# MatchboxARM.net
KiCad netlist of a schematic drawn in EAGLE
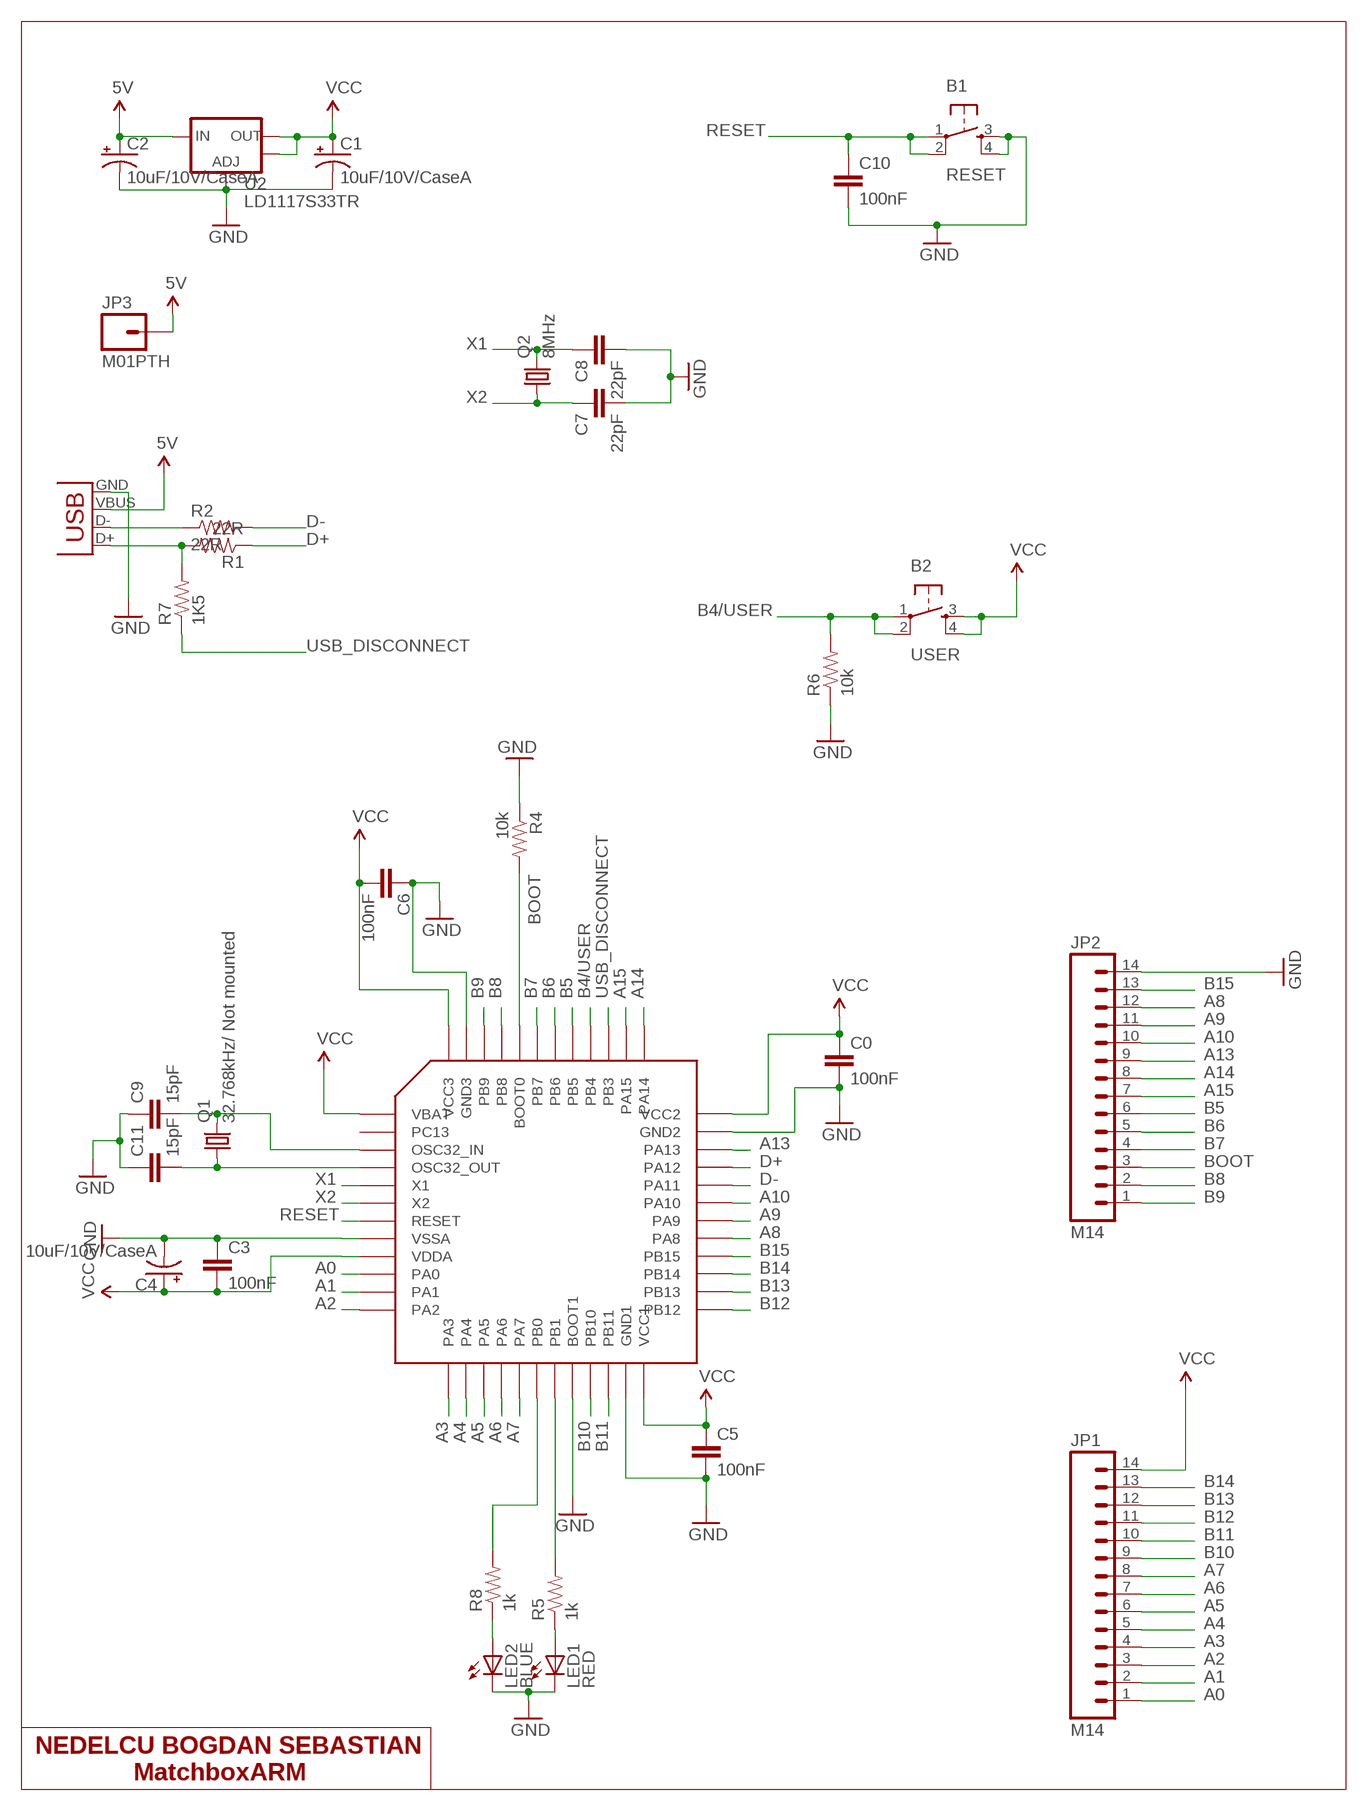
[diagram p0: schematic, sheet 1]

(export (version "E")
  (design (tool "Eeschema 10.0.6"))
  (components
    (comp (ref "B1")
      (value "RESET")
      (footprint "eagle-import:TACTILE_SWITCH_SMD")
      (libsource (lib "eagle-import") (part "TAC_SWITCHSMD"))
    )
    (comp (ref "B2")
      (value "USER")
      (footprint "eagle-import:TACTILE_SWITCH_SMD")
      (libsource (lib "eagle-import") (part "TAC_SWITCHSMD"))
    )
    (comp (ref "C0")
      (value "100nF")
      (footprint "eagle-import:0603-CAP")
      (libsource (lib "eagle-import") (part "CAP0603-CAP"))
    )
    (comp (ref "C1")
      (value "10uF/10V/CaseA")
      (footprint "eagle-import:EIA3216")
      (libsource (lib "eagle-import") (part "CAP_POL1206"))
    )
    (comp (ref "C2")
      (value "10uF/10V/CaseA")
      (footprint "eagle-import:EIA3216")
      (libsource (lib "eagle-import") (part "CAP_POL1206"))
    )
    (comp (ref "C3")
      (value "100nF")
      (footprint "eagle-import:0603-CAP")
      (libsource (lib "eagle-import") (part "CAP0603-CAP"))
    )
    (comp (ref "C4")
      (value "10uF/10V/CaseA")
      (footprint "eagle-import:EIA3216")
      (libsource (lib "eagle-import") (part "CAP_POL1206"))
    )
    (comp (ref "C5")
      (value "100nF")
      (footprint "eagle-import:0603-CAP")
      (libsource (lib "eagle-import") (part "CAP0603-CAP"))
    )
    (comp (ref "C6")
      (value "100nF")
      (footprint "eagle-import:0603-CAP")
      (libsource (lib "eagle-import") (part "CAP0603-CAP"))
    )
    (comp (ref "C7")
      (value "22pF")
      (footprint "eagle-import:0603-CAP")
      (libsource (lib "eagle-import") (part "CAP0603-CAP"))
    )
    (comp (ref "C8")
      (value "22pF")
      (footprint "eagle-import:0603-CAP")
      (libsource (lib "eagle-import") (part "CAP0603-CAP"))
    )
    (comp (ref "C9")
      (value "15pF")
      (footprint "eagle-import:0603-CAP")
      (libsource (lib "eagle-import") (part "CAP0603-CAP"))
    )
    (comp (ref "C10")
      (value "100nF")
      (footprint "eagle-import:0603-CAP")
      (libsource (lib "eagle-import") (part "CAP0603-CAP"))
    )
    (comp (ref "C11")
      (value "15pF")
      (footprint "eagle-import:0603-CAP")
      (libsource (lib "eagle-import") (part "CAP0603-CAP"))
    )
    (comp (ref "JP1")
      (value "M14")
      (footprint "eagle-import:1X14")
      (libsource (lib "eagle-import") (part "M14"))
    )
    (comp (ref "JP2")
      (value "M14")
      (footprint "eagle-import:1X14")
      (libsource (lib "eagle-import") (part "M14"))
    )
    (comp (ref "JP3")
      (value "M01PTH")
      (footprint "eagle-import:1X01")
      (libsource (lib "eagle-import") (part "M01PTH"))
    )
    (comp (ref "LED1")
      (value "RED")
      (footprint "eagle-import:LED-0603")
      (libsource (lib "eagle-import") (part "LED0603"))
    )
    (comp (ref "LED2")
      (value "BLUE")
      (footprint "eagle-import:LED-0603")
      (libsource (lib "eagle-import") (part "LED0603"))
    )
    (comp (ref "Q1")
      (value "32.768kHz/ Not mounted")
      (footprint "eagle-import:TC26V")
      (libsource (lib "eagle-import") (part "CRYSTALTC26V"))
    )
    (comp (ref "Q2")
      (value "8MHz")
      (footprint "eagle-import:CTS406")
      (libsource (lib "eagle-import") (part "CRYSTALCTS406"))
    )
    (comp (ref "R1")
      (value "22R")
      (footprint "eagle-import:0603-RES")
      (libsource (lib "eagle-import") (part "RESISTOR0603-RES"))
    )
    (comp (ref "R2")
      (value "22R")
      (footprint "eagle-import:0603-RES")
      (libsource (lib "eagle-import") (part "RESISTOR0603-RES"))
    )
    (comp (ref "R4")
      (value "10k")
      (footprint "eagle-import:0603-RES")
      (libsource (lib "eagle-import") (part "RESISTOR0603-RES"))
    )
    (comp (ref "R5")
      (value "1k")
      (footprint "eagle-import:0603-RES")
      (libsource (lib "eagle-import") (part "RESISTOR0603-RES"))
    )
    (comp (ref "R6")
      (value "10k")
      (footprint "eagle-import:0603-RES")
      (libsource (lib "eagle-import") (part "RESISTOR0603-RES"))
    )
    (comp (ref "R7")
      (value "1K5")
      (footprint "eagle-import:0603-RES")
      (libsource (lib "eagle-import") (part "RESISTOR0603-RES"))
    )
    (comp (ref "R8")
      (value "1k")
      (footprint "eagle-import:0603-RES")
      (libsource (lib "eagle-import") (part "RESISTOR0603-RES"))
    )
    (comp (ref "U1")
      (value "STM32F103CBT6")
      (footprint "eagle-import:STM32F103CXT6")
      (libsource (lib "eagle-import") (part "STM32F103CXT6"))
    )
    (comp (ref "U2")
      (value "LD1117S33TR")
      (footprint "eagle-import:SOT223")
      (libsource (lib "eagle-import") (part "V_REG_LM1117SOT223"))
    )
    (comp (ref "USB1")
      (value "miniUSBSMD")
      (footprint "eagle-import:USB-MINIB")
      (libsource (lib "eagle-import") (part "USBSMD"))
    )
  )
  (nets
    (net (code "1") (name "/A0") (class "Default")
      (node (ref "JP1") (pin "1") (pinfunction "1_1") (pintype "passive"))
      (node (ref "U1") (pin "10") (pinfunction "PA0_10") (pintype "bidirectional"))
    )
    (net (code "2") (name "/A1") (class "Default")
      (node (ref "JP1") (pin "2") (pinfunction "2_2") (pintype "passive"))
      (node (ref "U1") (pin "11") (pinfunction "PA1_11") (pintype "bidirectional"))
    )
    (net (code "3") (name "/A2") (class "Default")
      (node (ref "JP1") (pin "3") (pinfunction "3_3") (pintype "passive"))
      (node (ref "U1") (pin "12") (pinfunction "PA2_12") (pintype "bidirectional"))
    )
    (net (code "4") (name "/A3") (class "Default")
      (node (ref "JP1") (pin "4") (pinfunction "4_4") (pintype "passive"))
      (node (ref "U1") (pin "13") (pinfunction "PA3_13") (pintype "bidirectional"))
    )
    (net (code "5") (name "/A4") (class "Default")
      (node (ref "JP1") (pin "5") (pinfunction "5_5") (pintype "passive"))
      (node (ref "U1") (pin "14") (pinfunction "PA4_14") (pintype "bidirectional"))
    )
    (net (code "6") (name "/A5") (class "Default")
      (node (ref "JP1") (pin "6") (pinfunction "6_6") (pintype "passive"))
      (node (ref "U1") (pin "15") (pinfunction "PA5_15") (pintype "bidirectional"))
    )
    (net (code "7") (name "/A6") (class "Default")
      (node (ref "JP1") (pin "7") (pinfunction "7_7") (pintype "passive"))
      (node (ref "U1") (pin "16") (pinfunction "PA6_16") (pintype "bidirectional"))
    )
    (net (code "8") (name "/A7") (class "Default")
      (node (ref "JP1") (pin "8") (pinfunction "8_8") (pintype "passive"))
      (node (ref "U1") (pin "17") (pinfunction "PA7_17") (pintype "bidirectional"))
    )
    (net (code "9") (name "/A8") (class "Default")
      (node (ref "JP2") (pin "12") (pinfunction "12_12") (pintype "passive"))
      (node (ref "U1") (pin "29") (pinfunction "PA8_29") (pintype "bidirectional"))
    )
    (net (code "10") (name "/A9") (class "Default")
      (node (ref "JP2") (pin "11") (pinfunction "11_11") (pintype "passive"))
      (node (ref "U1") (pin "30") (pinfunction "PA9_30") (pintype "bidirectional"))
    )
    (net (code "11") (name "/A10") (class "Default")
      (node (ref "JP2") (pin "10") (pinfunction "10_10") (pintype "passive"))
      (node (ref "U1") (pin "31") (pinfunction "PA10_31") (pintype "bidirectional"))
    )
    (net (code "12") (name "/A13") (class "Default")
      (node (ref "JP2") (pin "9") (pinfunction "9_9") (pintype "passive"))
      (node (ref "U1") (pin "34") (pinfunction "PA13_34") (pintype "bidirectional"))
    )
    (net (code "13") (name "/A14") (class "Default")
      (node (ref "JP2") (pin "8") (pinfunction "8_8") (pintype "passive"))
      (node (ref "U1") (pin "37") (pinfunction "PA14_37") (pintype "bidirectional"))
    )
    (net (code "14") (name "/A15") (class "Default")
      (node (ref "JP2") (pin "7") (pinfunction "7_7") (pintype "passive"))
      (node (ref "U1") (pin "38") (pinfunction "PA15_38") (pintype "bidirectional"))
    )
    (net (code "15") (name "/B4{slash}USER") (class "Default")
      (node (ref "B2") (pin "1") (pinfunction "1_1") (pintype "passive"))
      (node (ref "B2") (pin "2") (pinfunction "2_2") (pintype "passive"))
      (node (ref "R6") (pin "2") (pinfunction "2_2") (pintype "passive"))
      (node (ref "U1") (pin "40") (pinfunction "PB4_40") (pintype "bidirectional"))
    )
    (net (code "16") (name "/B5") (class "Default")
      (node (ref "JP2") (pin "6") (pinfunction "6_6") (pintype "passive"))
      (node (ref "U1") (pin "41") (pinfunction "PB5_41") (pintype "bidirectional"))
    )
    (net (code "17") (name "/B6") (class "Default")
      (node (ref "JP2") (pin "5") (pinfunction "5_5") (pintype "passive"))
      (node (ref "U1") (pin "42") (pinfunction "PB6_42") (pintype "bidirectional"))
    )
    (net (code "18") (name "/B7") (class "Default")
      (node (ref "JP2") (pin "4") (pinfunction "4_4") (pintype "passive"))
      (node (ref "U1") (pin "43") (pinfunction "PB7_43") (pintype "bidirectional"))
    )
    (net (code "19") (name "/B8") (class "Default")
      (node (ref "JP2") (pin "2") (pinfunction "2_2") (pintype "passive"))
      (node (ref "U1") (pin "45") (pinfunction "PB8_45") (pintype "bidirectional"))
    )
    (net (code "20") (name "/B9") (class "Default")
      (node (ref "JP2") (pin "1") (pinfunction "1_1") (pintype "passive"))
      (node (ref "U1") (pin "46") (pinfunction "PB9_46") (pintype "bidirectional"))
    )
    (net (code "21") (name "/B10") (class "Default")
      (node (ref "JP1") (pin "9") (pinfunction "9_9") (pintype "passive"))
      (node (ref "U1") (pin "21") (pinfunction "PB10_21") (pintype "bidirectional"))
    )
    (net (code "22") (name "/B11") (class "Default")
      (node (ref "JP1") (pin "10") (pinfunction "10_10") (pintype "passive"))
      (node (ref "U1") (pin "22") (pinfunction "PB11_22") (pintype "bidirectional"))
    )
    (net (code "23") (name "/B12") (class "Default")
      (node (ref "JP1") (pin "11") (pinfunction "11_11") (pintype "passive"))
      (node (ref "U1") (pin "25") (pinfunction "PB12_25") (pintype "bidirectional"))
    )
    (net (code "24") (name "/B13") (class "Default")
      (node (ref "JP1") (pin "12") (pinfunction "12_12") (pintype "passive"))
      (node (ref "U1") (pin "26") (pinfunction "PB13_26") (pintype "bidirectional"))
    )
    (net (code "25") (name "/B14") (class "Default")
      (node (ref "JP1") (pin "13") (pinfunction "13_13") (pintype "passive"))
      (node (ref "U1") (pin "27") (pinfunction "PB14_27") (pintype "bidirectional"))
    )
    (net (code "26") (name "/B15") (class "Default")
      (node (ref "JP2") (pin "13") (pinfunction "13_13") (pintype "passive"))
      (node (ref "U1") (pin "28") (pinfunction "PB15_28") (pintype "bidirectional"))
    )
    (net (code "27") (name "/BOOT") (class "Default")
      (node (ref "JP2") (pin "3") (pinfunction "3_3") (pintype "passive"))
      (node (ref "R4") (pin "2") (pinfunction "2_2") (pintype "passive"))
      (node (ref "U1") (pin "44") (pinfunction "BOOT0_44") (pintype "bidirectional"))
    )
    (net (code "28") (name "/D+") (class "Default")
      (node (ref "R1") (pin "1") (pinfunction "1_1") (pintype "passive"))
      (node (ref "U1") (pin "33") (pinfunction "PA12_33") (pintype "bidirectional"))
    )
    (net (code "29") (name "/D-") (class "Default")
      (node (ref "R2") (pin "2") (pinfunction "2_2") (pintype "passive"))
      (node (ref "U1") (pin "32") (pinfunction "PA11_32") (pintype "bidirectional"))
    )
    (net (code "30") (name "/RESET") (class "Default")
      (node (ref "B1") (pin "1") (pinfunction "1_1") (pintype "passive"))
      (node (ref "B1") (pin "2") (pinfunction "2_2") (pintype "passive"))
      (node (ref "C10") (pin "1") (pinfunction "1_1") (pintype "passive"))
      (node (ref "U1") (pin "7") (pinfunction "RESET_7") (pintype "bidirectional"))
    )
    (net (code "31") (name "/USB_DISCONNECT") (class "Default")
      (node (ref "R7") (pin "1") (pinfunction "1_1") (pintype "passive"))
      (node (ref "U1") (pin "39") (pinfunction "PB3_39") (pintype "bidirectional"))
    )
    (net (code "32") (name "/X1") (class "Default")
      (node (ref "C8") (pin "1") (pinfunction "1_1") (pintype "passive"))
      (node (ref "Q2") (pin "3") (pinfunction "2_3") (pintype "passive"))
      (node (ref "U1") (pin "5") (pinfunction "X1_5") (pintype "bidirectional"))
    )
    (net (code "33") (name "/X2") (class "Default")
      (node (ref "C7") (pin "1") (pinfunction "1_1") (pintype "passive"))
      (node (ref "Q2") (pin "1") (pinfunction "1_1") (pintype "passive"))
      (node (ref "U1") (pin "6") (pinfunction "X2_6") (pintype "bidirectional"))
    )
    (net (code "34") (name "5V") (class "Default")
      (node (ref "C2") (pin "A") (pinfunction "+_A") (pintype "passive"))
      (node (ref "JP3") (pin "1") (pinfunction "1_1") (pintype "passive"))
      (node (ref "U2") (pin "3") (pinfunction "IN_3") (pintype "input"))
      (node (ref "USB1") (pin "VBUS") (pinfunction "VBUS_VBUS") (pintype "bidirectional"))
    )
    (net (code "35") (name "GND") (class "Default")
      (node (ref "B1") (pin "3") (pinfunction "3_3") (pintype "passive"))
      (node (ref "B1") (pin "4") (pinfunction "4_4") (pintype "passive"))
      (node (ref "C0") (pin "2") (pinfunction "2_2") (pintype "passive"))
      (node (ref "C1") (pin "C") (pinfunction "-_C") (pintype "passive"))
      (node (ref "C10") (pin "2") (pinfunction "2_2") (pintype "passive"))
      (node (ref "C11") (pin "1") (pinfunction "1_1") (pintype "passive"))
      (node (ref "C2") (pin "C") (pinfunction "-_C") (pintype "passive"))
      (node (ref "C3") (pin "1") (pinfunction "1_1") (pintype "passive"))
      (node (ref "C4") (pin "C") (pinfunction "-_C") (pintype "passive"))
      (node (ref "C5") (pin "2") (pinfunction "2_2") (pintype "passive"))
      (node (ref "C6") (pin "1") (pinfunction "1_1") (pintype "passive"))
      (node (ref "C7") (pin "2") (pinfunction "2_2") (pintype "passive"))
      (node (ref "C8") (pin "2") (pinfunction "2_2") (pintype "passive"))
      (node (ref "C9") (pin "1") (pinfunction "1_1") (pintype "passive"))
      (node (ref "JP2") (pin "14") (pinfunction "14_14") (pintype "passive"))
      (node (ref "LED1") (pin "C") (pinfunction "C_C") (pintype "passive"))
      (node (ref "LED2") (pin "C") (pinfunction "C_C") (pintype "passive"))
      (node (ref "R4") (pin "1") (pinfunction "1_1") (pintype "passive"))
      (node (ref "R6") (pin "1") (pinfunction "1_1") (pintype "passive"))
      (node (ref "U1") (pin "20") (pinfunction "BOOT1_20") (pintype "bidirectional"))
      (node (ref "U1") (pin "23") (pinfunction "GND1_23") (pintype "power_in"))
      (node (ref "U1") (pin "35") (pinfunction "GND2_35") (pintype "power_in"))
      (node (ref "U1") (pin "47") (pinfunction "GND3_47") (pintype "power_in"))
      (node (ref "U1") (pin "8") (pinfunction "VSSA_8") (pintype "power_in"))
      (node (ref "U2") (pin "1") (pinfunction "ADJ_1") (pintype "input"))
      (node (ref "USB1") (pin "GND") (pinfunction "GND_GND") (pintype "bidirectional"))
    )
    (net (code "36") (name "Net-(LED1-PadA)") (class "Default")
      (node (ref "LED1") (pin "A") (pinfunction "A_A") (pintype "passive"))
      (node (ref "R5") (pin "1") (pinfunction "1_1") (pintype "passive"))
    )
    (net (code "37") (name "Net-(LED2-PadA)") (class "Default")
      (node (ref "LED2") (pin "A") (pinfunction "A_A") (pintype "passive"))
      (node (ref "R8") (pin "1") (pinfunction "1_1") (pintype "passive"))
    )
    (net (code "38") (name "Net-(R1-Pad2)") (class "Default")
      (node (ref "R1") (pin "2") (pinfunction "2_2") (pintype "passive"))
      (node (ref "R7") (pin "2") (pinfunction "2_2") (pintype "passive"))
      (node (ref "USB1") (pin "D+") (pinfunction "D+_D+") (pintype "bidirectional"))
    )
    (net (code "39") (name "Net-(R2-Pad1)") (class "Default")
      (node (ref "R2") (pin "1") (pinfunction "1_1") (pintype "passive"))
      (node (ref "USB1") (pin "D-") (pinfunction "D-_D-") (pintype "bidirectional"))
    )
    (net (code "40") (name "Net-(U1-OSC32_IN)") (class "Default")
      (node (ref "C9") (pin "2") (pinfunction "2_2") (pintype "passive"))
      (node (ref "Q1") (pin "2") (pinfunction "2_2") (pintype "passive"))
      (node (ref "U1") (pin "3") (pinfunction "OSC32_IN_3") (pintype "bidirectional"))
    )
    (net (code "41") (name "Net-(U1-OSC32_OUT)") (class "Default")
      (node (ref "C11") (pin "2") (pinfunction "2_2") (pintype "passive"))
      (node (ref "Q1") (pin "1") (pinfunction "1_1") (pintype "passive"))
      (node (ref "U1") (pin "4") (pinfunction "OSC32_OUT_4") (pintype "bidirectional"))
    )
    (net (code "42") (name "Net-(U1-PB0)") (class "Default")
      (node (ref "R8") (pin "2") (pinfunction "2_2") (pintype "passive"))
      (node (ref "U1") (pin "18") (pinfunction "PB0_18") (pintype "bidirectional"))
    )
    (net (code "43") (name "Net-(U1-PB1)") (class "Default")
      (node (ref "R5") (pin "2") (pinfunction "2_2") (pintype "passive"))
      (node (ref "U1") (pin "19") (pinfunction "PB1_19") (pintype "bidirectional"))
    )
    (net (code "44") (name "VCC") (class "Default")
      (node (ref "B2") (pin "3") (pinfunction "3_3") (pintype "passive"))
      (node (ref "B2") (pin "4") (pinfunction "4_4") (pintype "passive"))
      (node (ref "C0") (pin "1") (pinfunction "1_1") (pintype "passive"))
      (node (ref "C1") (pin "A") (pinfunction "+_A") (pintype "passive"))
      (node (ref "C3") (pin "2") (pinfunction "2_2") (pintype "passive"))
      (node (ref "C4") (pin "A") (pinfunction "+_A") (pintype "passive"))
      (node (ref "C5") (pin "1") (pinfunction "1_1") (pintype "passive"))
      (node (ref "C6") (pin "2") (pinfunction "2_2") (pintype "passive"))
      (node (ref "JP1") (pin "14") (pinfunction "14_14") (pintype "passive"))
      (node (ref "U1") (pin "1") (pinfunction "VBAT_1") (pintype "power_in"))
      (node (ref "U1") (pin "24") (pinfunction "VCC1_24") (pintype "power_in"))
      (node (ref "U1") (pin "36") (pinfunction "VCC2_36") (pintype "power_in"))
      (node (ref "U1") (pin "48") (pinfunction "VCC3_48") (pintype "power_in"))
      (node (ref "U1") (pin "9") (pinfunction "VDDA_9") (pintype "power_in"))
      (node (ref "U2") (pin "2") (pinfunction "OUT_2") (pintype "output"))
      (node (ref "U2") (pin "4") (pinfunction "OUT_4") (pintype "output"))
    )
    (net (code "45") (name "unconnected-(U1-PC13-Pad2)") (class "Default")
      (node (ref "U1") (pin "2") (pinfunction "PC13_2") (pintype "bidirectional"))
    )
  )
)
